# Rainer_-_V0.net
KiCad netlist of a schematic drawn in EAGLE
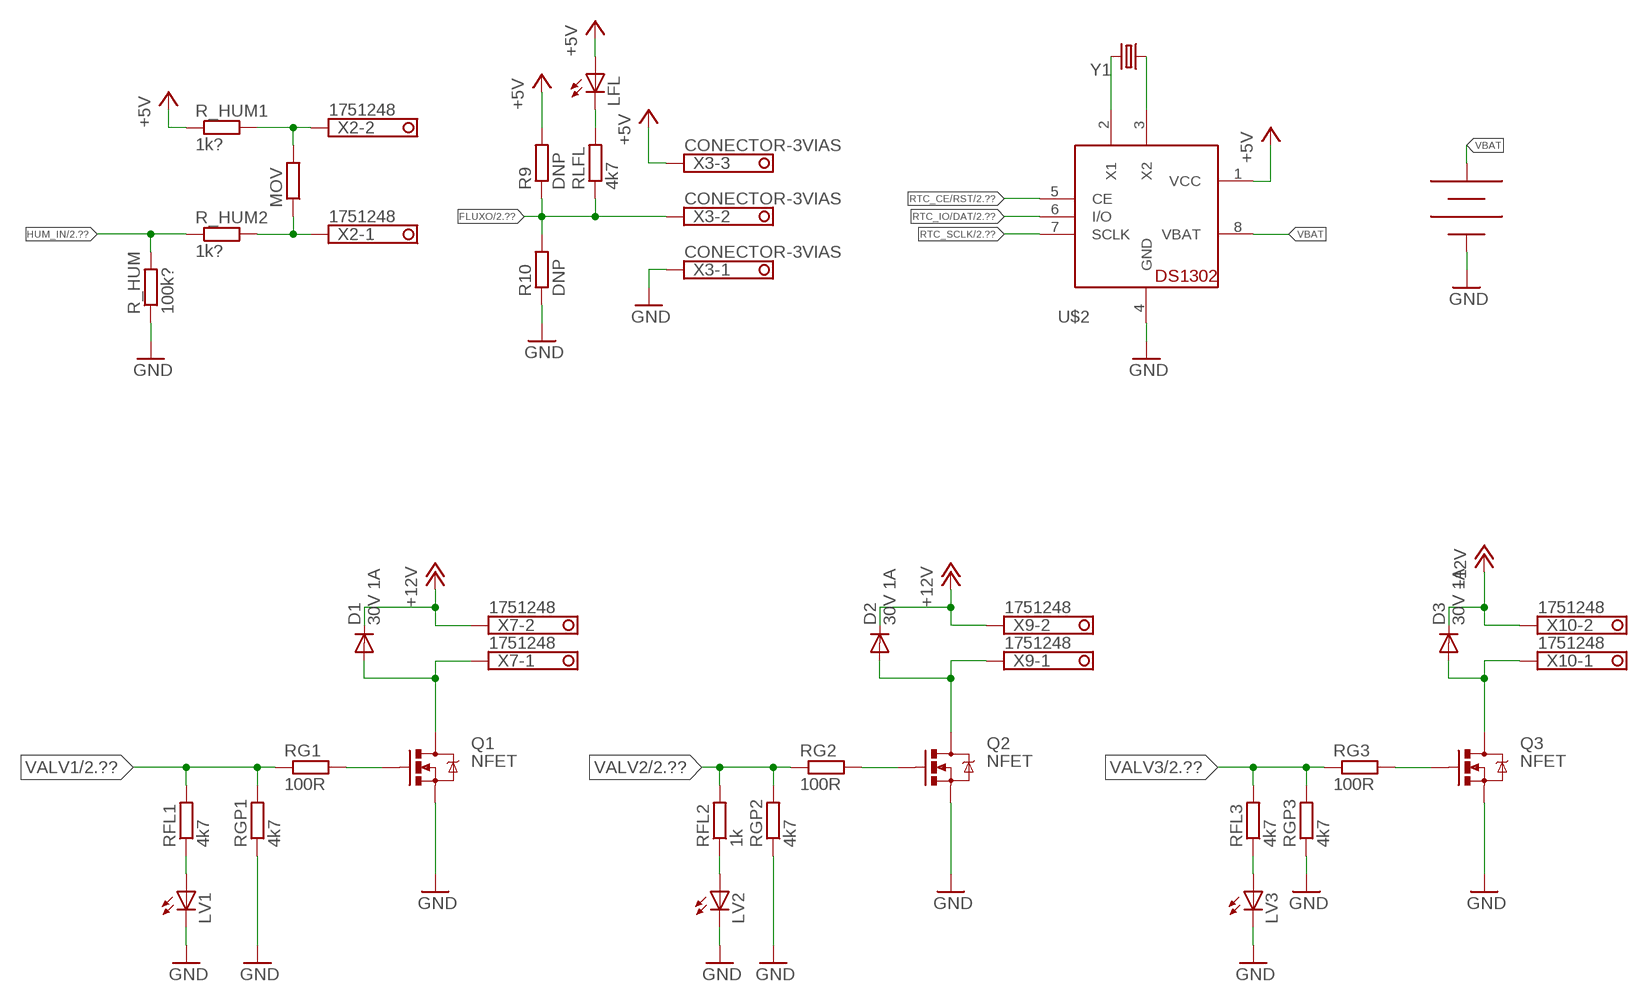
[diagram p0: schematic, sheet 1]
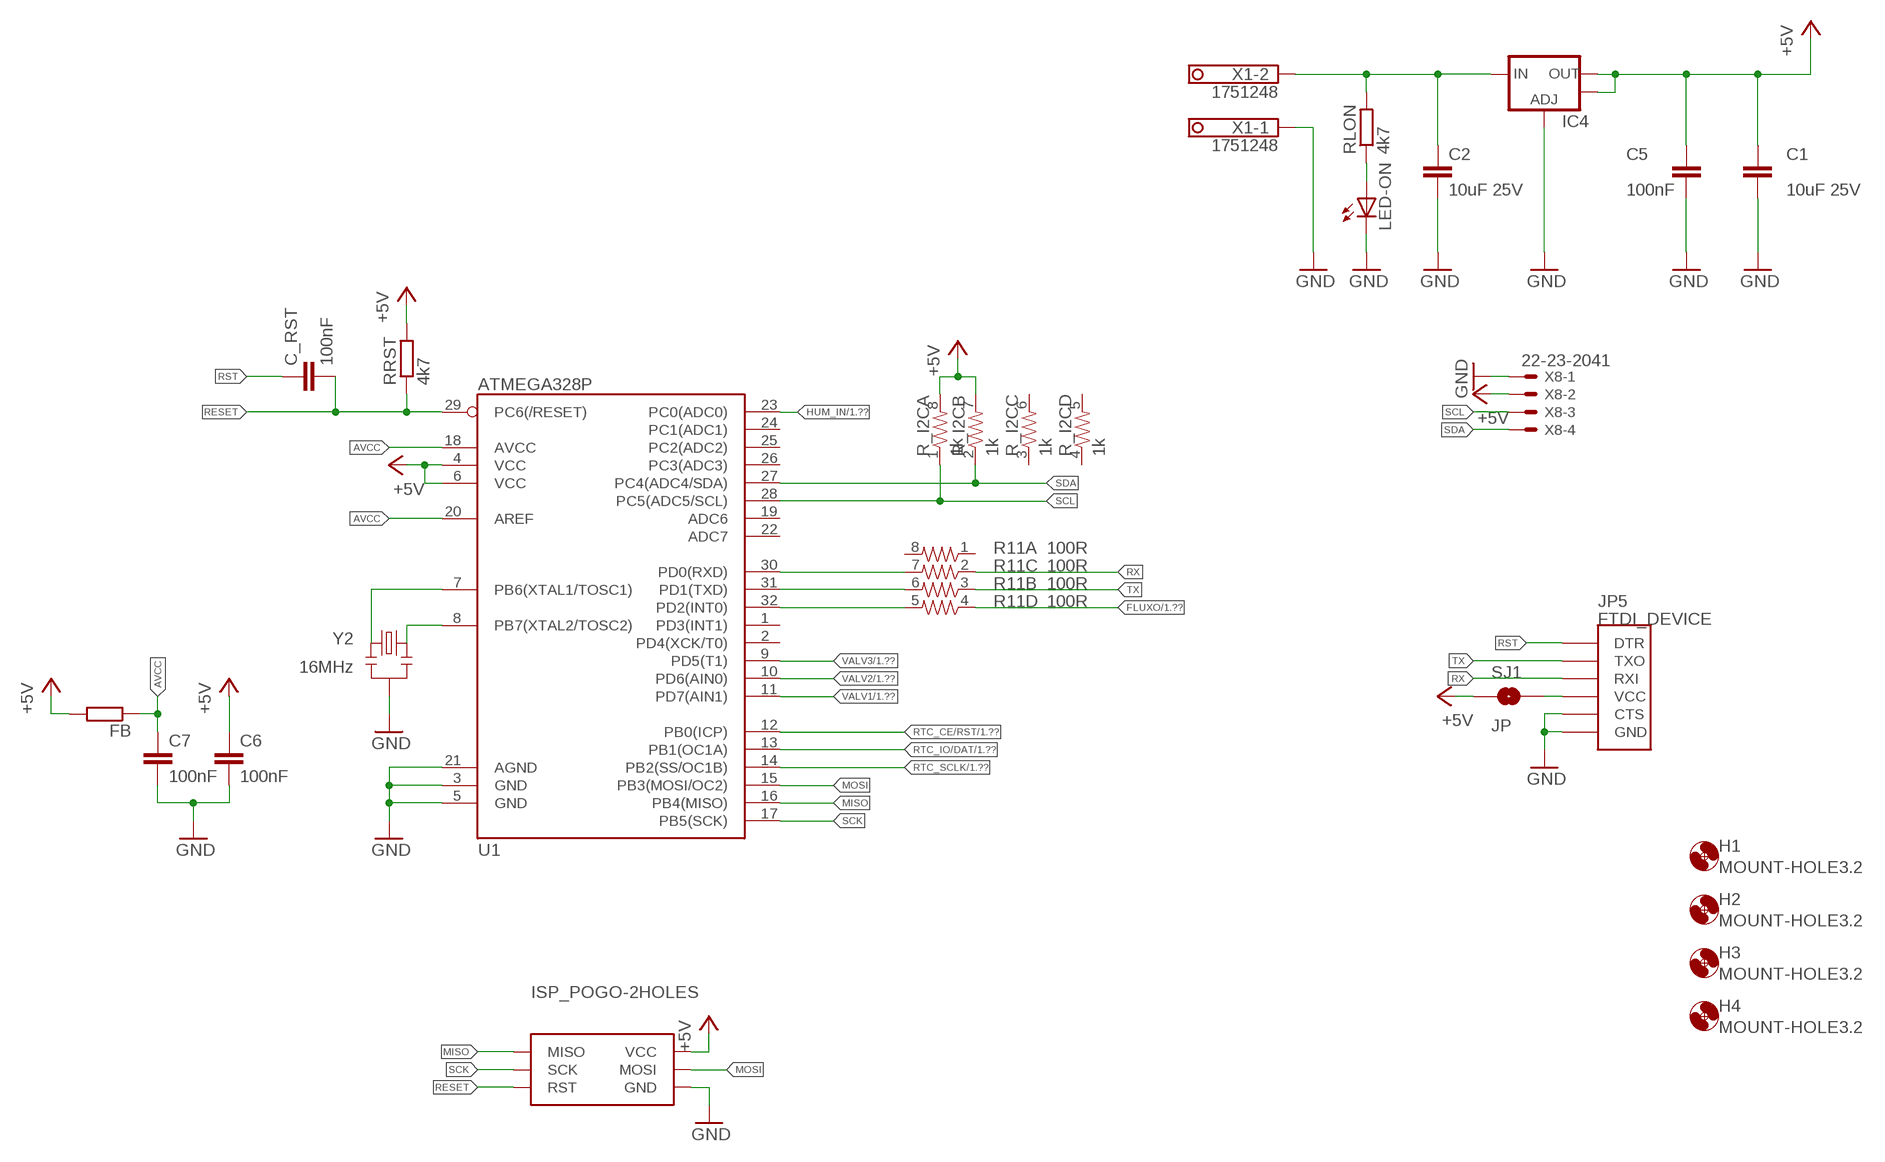
[diagram p1: schematic, sheet 2]

(export (version "E")
  (design (tool "Eeschema 10.0.6"))
  (components
    (comp (ref "C1")
      (value "10uF 25V")
      (footprint "eagle-import:C1210")
      (libsource (lib "eagle-import") (part "C-EUC1210"))
    )
    (comp (ref "C2")
      (value "10uF 25V")
      (footprint "eagle-import:C1210")
      (libsource (lib "eagle-import") (part "C-EUC1210"))
    )
    (comp (ref "C5")
      (value "100nF")
      (footprint "eagle-import:C0603")
      (libsource (lib "eagle-import") (part "C-EUC0603"))
    )
    (comp (ref "C6")
      (value "100nF")
      (footprint "eagle-import:C0603")
      (libsource (lib "eagle-import") (part "C-EUC0603"))
    )
    (comp (ref "C7")
      (value "100nF")
      (footprint "eagle-import:C0603")
      (libsource (lib "eagle-import") (part "C-EUC0603"))
    )
    (comp (ref "C_RST")
      (value "100nF")
      (footprint "eagle-import:C0603")
      (libsource (lib "eagle-import") (part "C-EUC0603"))
    )
    (comp (ref "FB")
      (value "R-EU_R0603")
      (footprint "eagle-import:R0603")
      (libsource (lib "eagle-import") (part "wes_R-EU_R0603"))
    )
    (comp (ref "H1")
      (value "MOUNT-HOLE3.2")
      (footprint "eagle-import:3,2")
      (libsource (lib "eagle-import") (part "MOUNT-HOLE3.2"))
    )
    (comp (ref "H2")
      (value "MOUNT-HOLE3.2")
      (footprint "eagle-import:3,2")
      (libsource (lib "eagle-import") (part "MOUNT-HOLE3.2"))
    )
    (comp (ref "H3")
      (value "MOUNT-HOLE3.2")
      (footprint "eagle-import:3,2")
      (libsource (lib "eagle-import") (part "MOUNT-HOLE3.2"))
    )
    (comp (ref "H4")
      (value "MOUNT-HOLE3.2")
      (footprint "eagle-import:3,2")
      (libsource (lib "eagle-import") (part "MOUNT-HOLE3.2"))
    )
    (comp (ref "IC4")
      (value "V_REG_LM1117SOT223")
      (footprint "eagle-import:SOT223")
      (libsource (lib "eagle-import") (part "V_REG_LM1117SOT223"))
    )
    (comp (ref "JP5")
      (value "FTDI_DEVICE")
      (footprint "eagle-import:FTDI_DEVICE_SIDE")
      (libsource (lib "eagle-import") (part "FTDI_DEVICE"))
    )
    (comp (ref "LED-ON")
      (value "LEDCHIP-LED0603")
      (footprint "eagle-import:CHIP-LED0603")
      (libsource (lib "eagle-import") (part "LEDCHIP-LED0603"))
    )
    (comp (ref "R11")
      (value "100R")
      (footprint "eagle-import:0603-ARV")
      (libsource (lib "eagle-import") (part "RESISTOR-ARRAY0603-ARV"))
    )
    (comp (ref "RLON")
      (value "4k7")
      (footprint "eagle-import:R0603")
      (libsource (lib "eagle-import") (part "wes_R-EU_R0603"))
    )
    (comp (ref "RRST")
      (value "4k7")
      (footprint "eagle-import:R0603")
      (libsource (lib "eagle-import") (part "wes_R-EU_R0603"))
    )
    (comp (ref "R_I2C")
      (value "1k")
      (footprint "eagle-import:0603-ARV")
      (libsource (lib "eagle-import") (part "RESISTOR-ARRAY0603-ARV"))
    )
    (comp (ref "SJ1")
      (value "JP")
      (footprint "eagle-import:SJ_2S-NOTRACE")
      (libsource (lib "eagle-import") (part "SOLDERJUMPER-OLDNC2"))
    )
    (comp (ref "U$1")
      (value "ISP_POGO-2HOLES")
      (footprint "eagle-import:ISP_POGO")
      (libsource (lib "eagle-import") (part "ISP_POGO-2HOLES"))
    )
    (comp (ref "U1")
      (value "ATMEGA328P")
      (footprint "eagle-import:TQFP32-08")
      (libsource (lib "eagle-import") (part "ATMEGA328_SMT"))
    )
    (comp (ref "X1")
      (value "1751248")
      (footprint "eagle-import:1751248")
      (libsource (lib "eagle-import") (part "1751248"))
    )
    (comp (ref "X8")
      (value "22-23-2041")
      (footprint "eagle-import:22-23-2041")
      (fields (field (name "MF") "MOLEX"))
      (libsource (lib "eagle-import") (part "22-23-2041"))
    )
    (comp (ref "Y2")
      (value "16MHz")
      (footprint "eagle-import:RESONATOR-SMD")
      (libsource (lib "eagle-import") (part "RESONATOR16MHZ"))
    )
    (comp (ref "D1")
      (value "30V 1A")
      (footprint "eagle-import:DO214AC")
      (libsource (lib "eagle-import") (part "DIODE-DO214AC"))
    )
    (comp (ref "D2")
      (value "30V 1A")
      (footprint "eagle-import:DO214AC")
      (libsource (lib "eagle-import") (part "DIODE-DO214AC"))
    )
    (comp (ref "D3")
      (value "30V 1A")
      (footprint "eagle-import:DO214AC")
      (libsource (lib "eagle-import") (part "DIODE-DO214AC"))
    )
    (comp (ref "LFL")
      (value "LEDCHIP-LED0603")
      (footprint "eagle-import:CHIP-LED0603")
      (libsource (lib "eagle-import") (part "LEDCHIP-LED0603"))
    )
    (comp (ref "LV1")
      (value "LEDCHIP-LED0603")
      (footprint "eagle-import:CHIP-LED0603")
      (libsource (lib "eagle-import") (part "LEDCHIP-LED0603"))
    )
    (comp (ref "LV2")
      (value "LEDCHIP-LED0603")
      (footprint "eagle-import:CHIP-LED0603")
      (libsource (lib "eagle-import") (part "LEDCHIP-LED0603"))
    )
    (comp (ref "LV3")
      (value "LEDCHIP-LED0603")
      (footprint "eagle-import:CHIP-LED0603")
      (libsource (lib "eagle-import") (part "LEDCHIP-LED0603"))
    )
    (comp (ref "MOV")
      (value "R-EU_0207/7")
      (footprint "eagle-import:0207_7")
      (libsource (lib "eagle-import") (part "R-EU_0207/7"))
    )
    (comp (ref "Q1")
      (value "NFET")
      (footprint "eagle-import:SOT23")
      (libsource (lib "eagle-import") (part "MOSFET-NCHANNELBSS138"))
    )
    (comp (ref "Q2")
      (value "NFET")
      (footprint "eagle-import:SOT23")
      (libsource (lib "eagle-import") (part "MOSFET-NCHANNELBSS138"))
    )
    (comp (ref "Q3")
      (value "NFET")
      (footprint "eagle-import:SOT23")
      (libsource (lib "eagle-import") (part "MOSFET-NCHANNELBSS138"))
    )
    (comp (ref "R9")
      (value "DNP")
      (footprint "eagle-import:R0603")
      (libsource (lib "eagle-import") (part "wes_R-EU_R0603"))
    )
    (comp (ref "R10")
      (value "DNP")
      (footprint "eagle-import:R0603")
      (libsource (lib "eagle-import") (part "wes_R-EU_R0603"))
    )
    (comp (ref "RFL1")
      (value "4k7")
      (footprint "eagle-import:R0603")
      (libsource (lib "eagle-import") (part "wes_R-EU_R0603"))
    )
    (comp (ref "RFL2")
      (value "1k")
      (footprint "eagle-import:R0603")
      (libsource (lib "eagle-import") (part "wes_R-EU_R0603"))
    )
    (comp (ref "RFL3")
      (value "4k7")
      (footprint "eagle-import:R0603")
      (libsource (lib "eagle-import") (part "wes_R-EU_R0603"))
    )
    (comp (ref "RG1")
      (value "100R")
      (footprint "eagle-import:R0603")
      (libsource (lib "eagle-import") (part "wes_R-EU_R0603"))
    )
    (comp (ref "RG2")
      (value "100R")
      (footprint "eagle-import:R0603")
      (libsource (lib "eagle-import") (part "wes_R-EU_R0603"))
    )
    (comp (ref "RG3")
      (value "100R")
      (footprint "eagle-import:R0603")
      (libsource (lib "eagle-import") (part "wes_R-EU_R0603"))
    )
    (comp (ref "RGP1")
      (value "4k7")
      (footprint "eagle-import:R0603")
      (libsource (lib "eagle-import") (part "wes_R-EU_R0603"))
    )
    (comp (ref "RGP2")
      (value "4k7")
      (footprint "eagle-import:R0603")
      (libsource (lib "eagle-import") (part "wes_R-EU_R0603"))
    )
    (comp (ref "RGP3")
      (value "4k7")
      (footprint "eagle-import:R0603")
      (libsource (lib "eagle-import") (part "wes_R-EU_R0603"))
    )
    (comp (ref "RLFL")
      (value "4k7")
      (footprint "eagle-import:R0603")
      (libsource (lib "eagle-import") (part "wes_R-EU_R0603"))
    )
    (comp (ref "R_HUM")
      (value "100k?")
      (footprint "eagle-import:R0603")
      (libsource (lib "eagle-import") (part "wes_R-EU_R0603"))
    )
    (comp (ref "R_HUM1")
      (value "1k?")
      (footprint "eagle-import:R0603")
      (libsource (lib "eagle-import") (part "wes_R-EU_R0603"))
    )
    (comp (ref "R_HUM2")
      (value "1k?")
      (footprint "eagle-import:R0603")
      (libsource (lib "eagle-import") (part "wes_R-EU_R0603"))
    )
    (comp (ref "U$2")
      (value "DS1302")
      (footprint "eagle-import:DIL08-ROUND")
      (libsource (lib "eagle-import") (part "DS1302"))
    )
    (comp (ref "U$4")
      (value "CR2032")
      (footprint "eagle-import:CR2032-A")
      (libsource (lib "eagle-import") (part "CR2032"))
    )
    (comp (ref "X2")
      (value "1751248")
      (footprint "eagle-import:1751248")
      (libsource (lib "eagle-import") (part "1751248"))
    )
    (comp (ref "X3")
      (value "CONECTOR-3VIAS")
      (footprint "eagle-import:3.5MM-3VIAS")
      (libsource (lib "eagle-import") (part "CONECTOR-3VIAS"))
    )
    (comp (ref "X7")
      (value "1751248")
      (footprint "eagle-import:1751248")
      (libsource (lib "eagle-import") (part "1751248"))
    )
    (comp (ref "X9")
      (value "1751248")
      (footprint "eagle-import:1751248")
      (libsource (lib "eagle-import") (part "1751248"))
    )
    (comp (ref "X10")
      (value "1751248")
      (footprint "eagle-import:1751248")
      (libsource (lib "eagle-import") (part "1751248"))
    )
    (comp (ref "Y1")
      (value "CRYSTAL")
      (footprint "eagle-import:TC26V")
      (libsource (lib "eagle-import") (part "CRYSTAL"))
    )
  )
  (nets
    (net (code "1") (name "+5V") (class "Default")
      (node (ref "C1") (pin "1") (pinfunction "1_1") (pintype "passive"))
      (node (ref "C5") (pin "1") (pinfunction "1_1") (pintype "passive"))
      (node (ref "C6") (pin "1") (pinfunction "1_1") (pintype "passive"))
      (node (ref "FB") (pin "2") (pinfunction "2_2") (pintype "passive"))
      (node (ref "IC4") (pin "2") (pinfunction "OUT_2") (pintype "output"))
      (node (ref "IC4") (pin "4") (pinfunction "OUT_4") (pintype "output"))
      (node (ref "LFL") (pin "A") (pinfunction "A_A") (pintype "passive"))
      (node (ref "R9") (pin "2") (pinfunction "2_2") (pintype "passive"))
      (node (ref "RRST") (pin "2") (pinfunction "2_2") (pintype "passive"))
      (node (ref "R_HUM1") (pin "1") (pinfunction "1_1") (pintype "passive"))
      (node (ref "R_I2C") (pin "7") (pinfunction "2_7") (pintype "passive"))
      (node (ref "R_I2C") (pin "8") (pinfunction "2_8") (pintype "passive"))
      (node (ref "SJ1") (pin "1") (pinfunction "1_1") (pintype "passive"))
      (node (ref "U$1") (pin "VCC") (pinfunction "VCC_VCC") (pintype "bidirectional"))
      (node (ref "U$2") (pin "1") (pinfunction "VCC_1") (pintype "power_in"))
      (node (ref "U1") (pin "4") (pinfunction "VCC_4") (pintype "bidirectional"))
      (node (ref "U1") (pin "6") (pinfunction "VCC_6") (pintype "bidirectional"))
      (node (ref "X3") (pin "3") (pinfunction "K_3") (pintype "passive"))
      (node (ref "X8") (pin "2") (pinfunction "S_2") (pintype "passive"))
    )
    (net (code "2") (name "+12V") (class "Default")
      (node (ref "C2") (pin "1") (pinfunction "1_1") (pintype "passive"))
      (node (ref "D1") (pin "C") (pinfunction "C_C") (pintype "passive"))
      (node (ref "D2") (pin "C") (pinfunction "C_C") (pintype "passive"))
      (node (ref "D3") (pin "C") (pinfunction "C_C") (pintype "passive"))
      (node (ref "IC4") (pin "3") (pinfunction "IN_3") (pintype "input"))
      (node (ref "RLON") (pin "2") (pinfunction "2_2") (pintype "passive"))
      (node (ref "X1") (pin "2") (pinfunction "K_2") (pintype "passive"))
      (node (ref "X10") (pin "2") (pinfunction "K_2") (pintype "passive"))
      (node (ref "X7") (pin "2") (pinfunction "K_2") (pintype "passive"))
      (node (ref "X9") (pin "2") (pinfunction "K_2") (pintype "passive"))
    )
    (net (code "3") (name "AVCC") (class "Default")
      (node (ref "C7") (pin "1") (pinfunction "1_1") (pintype "passive"))
      (node (ref "FB") (pin "1") (pinfunction "1_1") (pintype "passive"))
      (node (ref "U1") (pin "18") (pinfunction "AVCC_18") (pintype "bidirectional"))
      (node (ref "U1") (pin "20") (pinfunction "AREF_20") (pintype "bidirectional"))
    )
    (net (code "4") (name "FLUXO") (class "Default")
      (node (ref "R10") (pin "2") (pinfunction "2_2") (pintype "passive"))
      (node (ref "R11") (pin "4") (pinfunction "1_4") (pintype "passive"))
      (node (ref "R9") (pin "1") (pinfunction "1_1") (pintype "passive"))
      (node (ref "RLFL") (pin "1") (pinfunction "1_1") (pintype "passive"))
      (node (ref "X3") (pin "2") (pinfunction "K_2") (pintype "passive"))
    )
    (net (code "5") (name "GND") (class "Default")
      (node (ref "C1") (pin "2") (pinfunction "2_2") (pintype "passive"))
      (node (ref "C2") (pin "2") (pinfunction "2_2") (pintype "passive"))
      (node (ref "C5") (pin "2") (pinfunction "2_2") (pintype "passive"))
      (node (ref "C6") (pin "2") (pinfunction "2_2") (pintype "passive"))
      (node (ref "C7") (pin "2") (pinfunction "2_2") (pintype "passive"))
      (node (ref "IC4") (pin "1") (pinfunction "ADJ_1") (pintype "input"))
      (node (ref "JP5") (pin "P$5") (pinfunction "CTS_P$5") (pintype "bidirectional"))
      (node (ref "JP5") (pin "P$6") (pinfunction "GND_P$6") (pintype "bidirectional"))
      (node (ref "LED-ON") (pin "C") (pinfunction "C_C") (pintype "passive"))
      (node (ref "LV1") (pin "C") (pinfunction "C_C") (pintype "passive"))
      (node (ref "LV2") (pin "C") (pinfunction "C_C") (pintype "passive"))
      (node (ref "LV3") (pin "C") (pinfunction "C_C") (pintype "passive"))
      (node (ref "Q1") (pin "2") (pinfunction "S_2") (pintype "passive"))
      (node (ref "Q2") (pin "2") (pinfunction "S_2") (pintype "passive"))
      (node (ref "Q3") (pin "2") (pinfunction "S_2") (pintype "passive"))
      (node (ref "R10") (pin "1") (pinfunction "1_1") (pintype "passive"))
      (node (ref "RGP1") (pin "1") (pinfunction "1_1") (pintype "passive"))
      (node (ref "RGP2") (pin "1") (pinfunction "1_1") (pintype "passive"))
      (node (ref "RGP3") (pin "1") (pinfunction "1_1") (pintype "passive"))
      (node (ref "R_HUM") (pin "1") (pinfunction "1_1") (pintype "passive"))
      (node (ref "U$1") (pin "GND") (pinfunction "GND_GND") (pintype "bidirectional"))
      (node (ref "U$2") (pin "4") (pinfunction "GND_4") (pintype "power_in"))
      (node (ref "U$4") (pin "P$1") (pinfunction "P$1_P$1") (pintype "bidirectional"))
      (node (ref "U1") (pin "21") (pinfunction "AGND_21") (pintype "bidirectional"))
      (node (ref "U1") (pin "3") (pinfunction "GND_3") (pintype "bidirectional"))
      (node (ref "U1") (pin "5") (pinfunction "GND_5") (pintype "bidirectional"))
      (node (ref "X1") (pin "1") (pinfunction "K_1") (pintype "passive"))
      (node (ref "X3") (pin "1") (pinfunction "K_1") (pintype "passive"))
      (node (ref "X8") (pin "1") (pinfunction "S_1") (pintype "passive"))
      (node (ref "Y2") (pin "2") (pinfunction "2_2") (pintype "passive"))
    )
    (net (code "6") (name "HUM_IN") (class "Default")
      (node (ref "R_HUM") (pin "2") (pinfunction "2_2") (pintype "passive"))
      (node (ref "R_HUM2") (pin "1") (pinfunction "1_1") (pintype "passive"))
      (node (ref "U1") (pin "23") (pinfunction "PC0(ADC0)_23") (pintype "bidirectional"))
    )
    (net (code "7") (name "MISO") (class "Default")
      (node (ref "U$1") (pin "MISO") (pinfunction "MISO_MISO") (pintype "bidirectional"))
      (node (ref "U1") (pin "16") (pinfunction "PB4(MISO)_16") (pintype "bidirectional"))
    )
    (net (code "8") (name "MOSI") (class "Default")
      (node (ref "U$1") (pin "MOSI") (pinfunction "MOSI_MOSI") (pintype "bidirectional"))
      (node (ref "U1") (pin "15") (pinfunction "PB3(MOSI/OC2)_15") (pintype "bidirectional"))
    )
    (net (code "9") (name "Net-(JP5-VCC)") (class "Default")
      (node (ref "JP5") (pin "P$4") (pinfunction "VCC_P$4") (pintype "bidirectional"))
      (node (ref "SJ1") (pin "2") (pinfunction "2_2") (pintype "passive"))
    )
    (net (code "10") (name "Net-(LED-ON-PadA)") (class "Default")
      (node (ref "LED-ON") (pin "A") (pinfunction "A_A") (pintype "passive"))
      (node (ref "RLON") (pin "1") (pinfunction "1_1") (pintype "passive"))
    )
    (net (code "11") (name "Net-(LFL-PadC)") (class "Default")
      (node (ref "LFL") (pin "C") (pinfunction "C_C") (pintype "passive"))
      (node (ref "RLFL") (pin "2") (pinfunction "2_2") (pintype "passive"))
    )
    (net (code "12") (name "Net-(LV1-PadA)") (class "Default")
      (node (ref "LV1") (pin "A") (pinfunction "A_A") (pintype "passive"))
      (node (ref "RFL1") (pin "1") (pinfunction "1_1") (pintype "passive"))
    )
    (net (code "13") (name "Net-(LV2-PadA)") (class "Default")
      (node (ref "LV2") (pin "A") (pinfunction "A_A") (pintype "passive"))
      (node (ref "RFL2") (pin "1") (pinfunction "1_1") (pintype "passive"))
    )
    (net (code "14") (name "Net-(LV3-PadA)") (class "Default")
      (node (ref "LV3") (pin "A") (pinfunction "A_A") (pintype "passive"))
      (node (ref "RFL3") (pin "1") (pinfunction "1_1") (pintype "passive"))
    )
    (net (code "15") (name "Net-(Q1-D)") (class "Default")
      (node (ref "D1") (pin "A") (pinfunction "A_A") (pintype "passive"))
      (node (ref "Q1") (pin "3") (pinfunction "D_3") (pintype "passive"))
      (node (ref "X7") (pin "1") (pinfunction "K_1") (pintype "passive"))
    )
    (net (code "16") (name "Net-(Q1-G)") (class "Default")
      (node (ref "Q1") (pin "1") (pinfunction "G_1") (pintype "passive"))
      (node (ref "RG1") (pin "2") (pinfunction "2_2") (pintype "passive"))
    )
    (net (code "17") (name "Net-(Q2-D)") (class "Default")
      (node (ref "D2") (pin "A") (pinfunction "A_A") (pintype "passive"))
      (node (ref "Q2") (pin "3") (pinfunction "D_3") (pintype "passive"))
      (node (ref "X9") (pin "1") (pinfunction "K_1") (pintype "passive"))
    )
    (net (code "18") (name "Net-(Q2-G)") (class "Default")
      (node (ref "Q2") (pin "1") (pinfunction "G_1") (pintype "passive"))
      (node (ref "RG2") (pin "2") (pinfunction "2_2") (pintype "passive"))
    )
    (net (code "19") (name "Net-(Q3-D)") (class "Default")
      (node (ref "D3") (pin "A") (pinfunction "A_A") (pintype "passive"))
      (node (ref "Q3") (pin "3") (pinfunction "D_3") (pintype "passive"))
      (node (ref "X10") (pin "1") (pinfunction "K_1") (pintype "passive"))
    )
    (net (code "20") (name "Net-(Q3-G)") (class "Default")
      (node (ref "Q3") (pin "1") (pinfunction "G_1") (pintype "passive"))
      (node (ref "RG3") (pin "2") (pinfunction "2_2") (pintype "passive"))
    )
    (net (code "21") (name "Net-(R11B-2)") (class "Default")
      (node (ref "R11") (pin "7") (pinfunction "2_7") (pintype "passive"))
      (node (ref "U1") (pin "30") (pinfunction "PD0(RXD)_30") (pintype "bidirectional"))
    )
    (net (code "22") (name "Net-(R11C-2)") (class "Default")
      (node (ref "R11") (pin "6") (pinfunction "2_6") (pintype "passive"))
      (node (ref "U1") (pin "31") (pinfunction "PD1(TXD)_31") (pintype "bidirectional"))
    )
    (net (code "23") (name "Net-(R11D-2)") (class "Default")
      (node (ref "R11") (pin "5") (pinfunction "2_5") (pintype "passive"))
      (node (ref "U1") (pin "32") (pinfunction "PD2(INT0)_32") (pintype "bidirectional"))
    )
    (net (code "24") (name "Net-(U$2-X1)") (class "Default")
      (node (ref "U$2") (pin "2") (pinfunction "X1_2") (pintype "passive"))
      (node (ref "Y1") (pin "2") (pinfunction "2_2") (pintype "passive"))
    )
    (net (code "25") (name "Net-(U$2-X2)") (class "Default")
      (node (ref "U$2") (pin "3") (pinfunction "X2_3") (pintype "passive"))
      (node (ref "Y1") (pin "1") (pinfunction "1_1") (pintype "passive"))
    )
    (net (code "26") (name "Net-(U1-PB6(XTAL1{slash}TOSC1))") (class "Default")
      (node (ref "U1") (pin "7") (pinfunction "PB6(XTAL1/TOSC1)_7") (pintype "bidirectional"))
      (node (ref "Y2") (pin "1") (pinfunction "1_1") (pintype "passive"))
    )
    (net (code "27") (name "Net-(U1-PB7(XTAL2{slash}TOSC2))") (class "Default")
      (node (ref "U1") (pin "8") (pinfunction "PB7(XTAL2/TOSC2)_8") (pintype "bidirectional"))
      (node (ref "Y2") (pin "3") (pinfunction "3_3") (pintype "passive"))
    )
    (net (code "28") (name "Net-(X2A-K)") (class "Default")
      (node (ref "MOV") (pin "1") (pinfunction "1_1") (pintype "passive"))
      (node (ref "R_HUM2") (pin "2") (pinfunction "2_2") (pintype "passive"))
      (node (ref "X2") (pin "1") (pinfunction "K_1") (pintype "passive"))
    )
    (net (code "29") (name "Net-(X2B-K)") (class "Default")
      (node (ref "MOV") (pin "2") (pinfunction "2_2") (pintype "passive"))
      (node (ref "R_HUM1") (pin "2") (pinfunction "2_2") (pintype "passive"))
      (node (ref "X2") (pin "2") (pinfunction "K_2") (pintype "passive"))
    )
    (net (code "30") (name "RESET") (class "Default")
      (node (ref "C_RST") (pin "2") (pinfunction "2_2") (pintype "passive"))
      (node (ref "RRST") (pin "1") (pinfunction "1_1") (pintype "passive"))
      (node (ref "U$1") (pin "RST") (pinfunction "RST_RST") (pintype "bidirectional"))
      (node (ref "U1") (pin "29") (pinfunction "PC6(/RESET)_29") (pintype "bidirectional"))
    )
    (net (code "31") (name "RST") (class "Default")
      (node (ref "C_RST") (pin "1") (pinfunction "1_1") (pintype "passive"))
      (node (ref "JP5") (pin "P$1") (pinfunction "DTR_P$1") (pintype "bidirectional"))
    )
    (net (code "32") (name "RTC_CE{slash}RST") (class "Default")
      (node (ref "U$2") (pin "5") (pinfunction "CE_5") (pintype "input"))
      (node (ref "U1") (pin "12") (pinfunction "PB0(ICP)_12") (pintype "bidirectional"))
    )
    (net (code "33") (name "RTC_IO{slash}DAT") (class "Default")
      (node (ref "U$2") (pin "6") (pinfunction "I/O_6") (pintype "bidirectional"))
      (node (ref "U1") (pin "13") (pinfunction "PB1(OC1A)_13") (pintype "bidirectional"))
    )
    (net (code "34") (name "RTC_SCLK") (class "Default")
      (node (ref "U$2") (pin "7") (pinfunction "SCLK_7") (pintype "input"))
      (node (ref "U1") (pin "14") (pinfunction "PB2(SS/OC1B)_14") (pintype "bidirectional"))
    )
    (net (code "35") (name "RX") (class "Default")
      (node (ref "JP5") (pin "P$3") (pinfunction "RXI_P$3") (pintype "bidirectional"))
      (node (ref "R11") (pin "2") (pinfunction "1_2") (pintype "passive"))
    )
    (net (code "36") (name "SCK") (class "Default")
      (node (ref "U$1") (pin "SCK") (pinfunction "SCK_SCK") (pintype "bidirectional"))
      (node (ref "U1") (pin "17") (pinfunction "PB5(SCK)_17") (pintype "bidirectional"))
    )
    (net (code "37") (name "SCL") (class "Default")
      (node (ref "R_I2C") (pin "1") (pinfunction "1_1") (pintype "passive"))
      (node (ref "U1") (pin "28") (pinfunction "PC5(ADC5/SCL)_28") (pintype "bidirectional"))
      (node (ref "X8") (pin "3") (pinfunction "S_3") (pintype "passive"))
    )
    (net (code "38") (name "SDA") (class "Default")
      (node (ref "R_I2C") (pin "2") (pinfunction "1_2") (pintype "passive"))
      (node (ref "U1") (pin "27") (pinfunction "PC4(ADC4/SDA)_27") (pintype "bidirectional"))
      (node (ref "X8") (pin "4") (pinfunction "S_4") (pintype "passive"))
    )
    (net (code "39") (name "TX") (class "Default")
      (node (ref "JP5") (pin "P$2") (pinfunction "TXO_P$2") (pintype "bidirectional"))
      (node (ref "R11") (pin "3") (pinfunction "1_3") (pintype "passive"))
    )
    (net (code "40") (name "VALV1") (class "Default")
      (node (ref "RFL1") (pin "2") (pinfunction "2_2") (pintype "passive"))
      (node (ref "RG1") (pin "1") (pinfunction "1_1") (pintype "passive"))
      (node (ref "RGP1") (pin "2") (pinfunction "2_2") (pintype "passive"))
      (node (ref "U1") (pin "11") (pinfunction "PD7(AIN1)_11") (pintype "bidirectional"))
    )
    (net (code "41") (name "VALV2") (class "Default")
      (node (ref "RFL2") (pin "2") (pinfunction "2_2") (pintype "passive"))
      (node (ref "RG2") (pin "1") (pinfunction "1_1") (pintype "passive"))
      (node (ref "RGP2") (pin "2") (pinfunction "2_2") (pintype "passive"))
      (node (ref "U1") (pin "10") (pinfunction "PD6(AIN0)_10") (pintype "bidirectional"))
    )
    (net (code "42") (name "VALV3") (class "Default")
      (node (ref "RFL3") (pin "2") (pinfunction "2_2") (pintype "passive"))
      (node (ref "RG3") (pin "1") (pinfunction "1_1") (pintype "passive"))
      (node (ref "RGP3") (pin "2") (pinfunction "2_2") (pintype "passive"))
      (node (ref "U1") (pin "9") (pinfunction "PD5(T1)_9") (pintype "bidirectional"))
    )
    (net (code "43") (name "VBAT") (class "Default")
      (node (ref "U$2") (pin "8") (pinfunction "VBAT_8") (pintype "power_in"))
      (node (ref "U$4") (pin "P$2") (pinfunction "P$2_P$2") (pintype "bidirectional"))
    )
    (net (code "44") (name "unconnected-(R11-Pad1)") (class "Default")
      (node (ref "R11") (pin "1") (pinfunction "1_1") (pintype "passive"))
    )
    (net (code "45") (name "unconnected-(R11A-2-Pad8)") (class "Default")
      (node (ref "R11") (pin "8") (pinfunction "2_8") (pintype "passive"))
    )
    (net (code "46") (name "unconnected-(R_I2CC-1-Pad3)") (class "Default")
      (node (ref "R_I2C") (pin "3") (pinfunction "1_3") (pintype "passive"))
    )
    (net (code "47") (name "unconnected-(R_I2CC-2-Pad6)") (class "Default")
      (node (ref "R_I2C") (pin "6") (pinfunction "2_6") (pintype "passive"))
    )
    (net (code "48") (name "unconnected-(R_I2CD-1-Pad4)") (class "Default")
      (node (ref "R_I2C") (pin "4") (pinfunction "1_4") (pintype "passive"))
    )
    (net (code "49") (name "unconnected-(R_I2CD-2-Pad5)") (class "Default")
      (node (ref "R_I2C") (pin "5") (pinfunction "2_5") (pintype "passive"))
    )
    (net (code "50") (name "unconnected-(U1-ADC6-Pad19)") (class "Default")
      (node (ref "U1") (pin "19") (pinfunction "ADC6_19") (pintype "bidirectional"))
    )
    (net (code "51") (name "unconnected-(U1-ADC7-Pad22)") (class "Default")
      (node (ref "U1") (pin "22") (pinfunction "ADC7_22") (pintype "bidirectional"))
    )
    (net (code "52") (name "unconnected-(U1-PC1(ADC1)-Pad24)") (class "Default")
      (node (ref "U1") (pin "24") (pinfunction "PC1(ADC1)_24") (pintype "bidirectional"))
    )
    (net (code "53") (name "unconnected-(U1-PC2(ADC2)-Pad25)") (class "Default")
      (node (ref "U1") (pin "25") (pinfunction "PC2(ADC2)_25") (pintype "bidirectional"))
    )
    (net (code "54") (name "unconnected-(U1-PC3(ADC3)-Pad26)") (class "Default")
      (node (ref "U1") (pin "26") (pinfunction "PC3(ADC3)_26") (pintype "bidirectional"))
    )
    (net (code "55") (name "unconnected-(U1-PD3(INT1)-Pad1)") (class "Default")
      (node (ref "U1") (pin "1") (pinfunction "PD3(INT1)_1") (pintype "bidirectional"))
    )
    (net (code "56") (name "unconnected-(U1-PD4(XCK{slash}T0)-Pad2)") (class "Default")
      (node (ref "U1") (pin "2") (pinfunction "PD4(XCK/T0)_2") (pintype "bidirectional"))
    )
  )
)
